# Power.net
KiCad netlist of a schematic drawn in Altium Designer
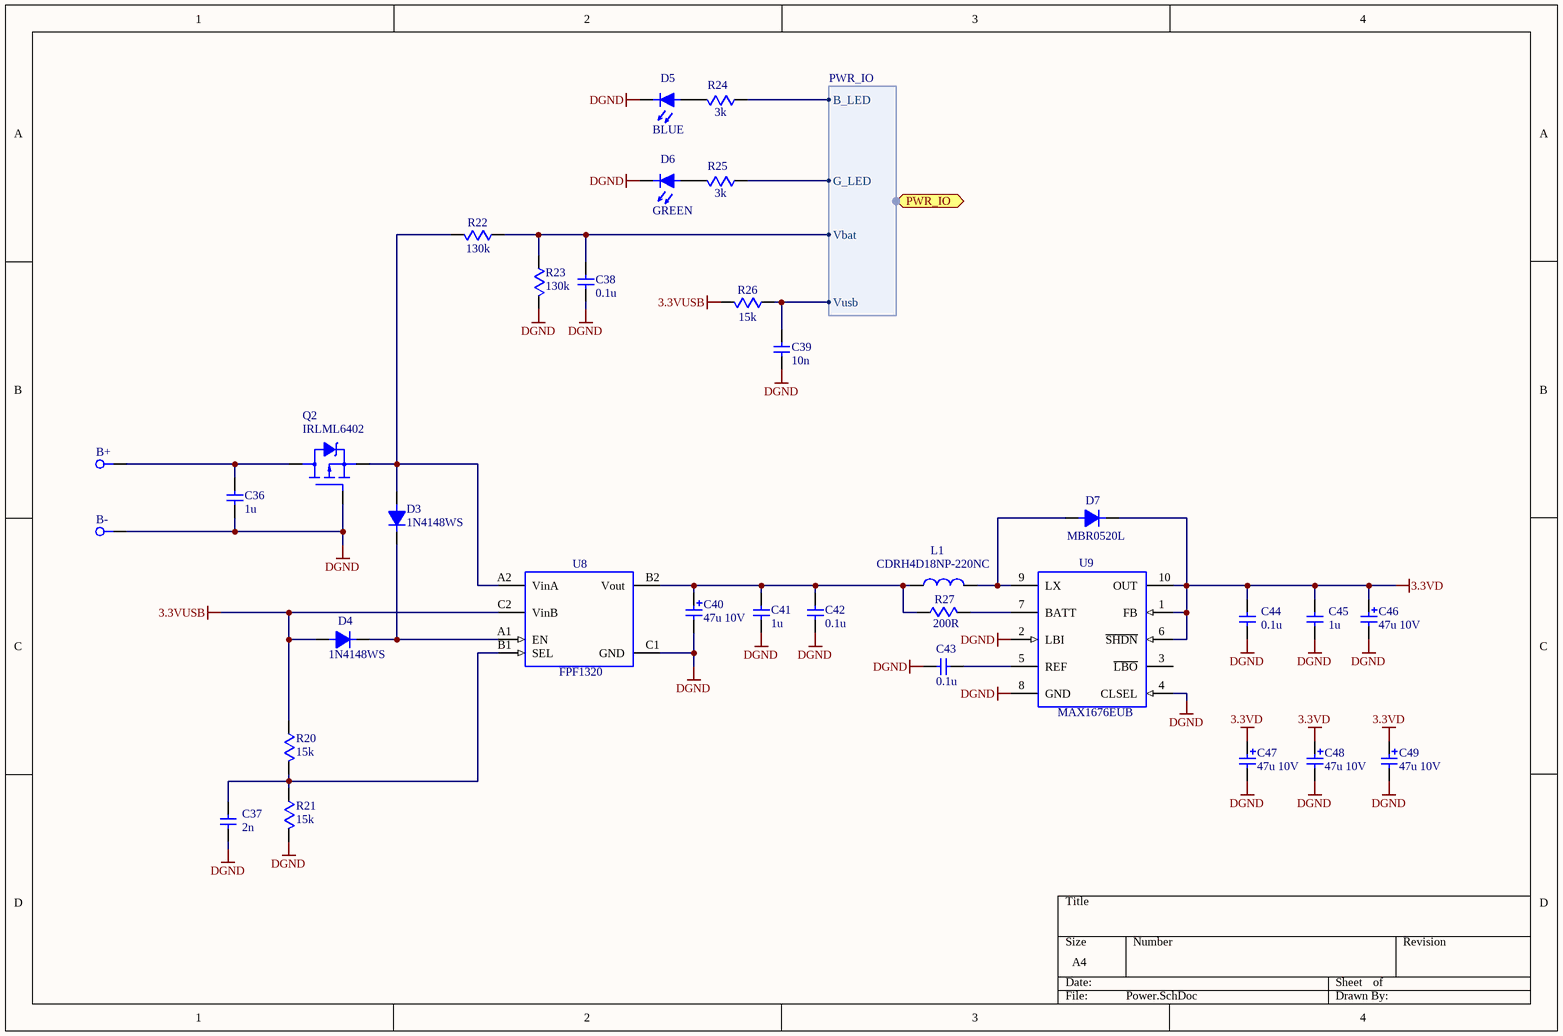
[diagram p0: Power.SchDoc]

(export (version "E")
  (design (tool "Eeschema 10.0.6"))
  (components
    (comp (ref "B+") (value "TH HOLE") (footprint "1.0MM PAD") (libsource (lib "My_lib") (part "TH HOLE")))
    (comp (ref "B-") (value "TH HOLE") (footprint "1.0MM PAD") (libsource (lib "My_lib") (part "TH HOLE")))
    (comp (ref "C36") (value "1u") (footprint "SMD/C/0603") (libsource (lib "My_lib") (part "Capacitor")))
    (comp (ref "C37") (value "2n") (footprint "SMD/C/0603") (libsource (lib "") (part "Capacitor_1")))
    (comp (ref "C38") (value "0.1u") (footprint "SMD/C/0603") (libsource (lib "My_lib") (part "Capacitor")))
    (comp (ref "C39") (value "10n") (footprint "SMD/C/0603") (libsource (lib "My_lib") (part "Capacitor")))
    (comp (ref "C40")
      (value "47u 10V")
      (footprint "SMD/C/TAJ-B")
      (libsource (lib "My_lib") (part "Capacitor Pol"))
    )
    (comp (ref "C41") (value "1u") (footprint "SMD/C/0603") (libsource (lib "My_lib") (part "Capacitor")))
    (comp (ref "C42") (value "0.1u") (footprint "SMD/C/0603") (libsource (lib "My_lib") (part "Capacitor")))
    (comp (ref "C43") (value "0.1u") (footprint "SMD/C/0603") (libsource (lib "") (part "Capacitor_1")))
    (comp (ref "C44") (value "0.1u") (footprint "SMD/C/0603") (libsource (lib "") (part "Capacitor_1")))
    (comp (ref "C45") (value "1u") (footprint "SMD/C/0603") (libsource (lib "") (part "Capacitor_1")))
    (comp (ref "C46")
      (value "47u 10V")
      (footprint "SMD/C/TAJ-B")
      (libsource (lib "My_lib") (part "Capacitor Pol"))
    )
    (comp (ref "C47")
      (value "47u 10V")
      (footprint "SMD/C/TAJ-B")
      (libsource (lib "My_lib") (part "Capacitor Pol"))
    )
    (comp (ref "C48")
      (value "47u 10V")
      (footprint "SMD/C/TAJ-B")
      (libsource (lib "My_lib") (part "Capacitor Pol"))
    )
    (comp (ref "C49")
      (value "47u 10V")
      (footprint "SMD/C/TAJ-B")
      (libsource (lib "My_lib") (part "Capacitor Pol"))
    )
    (comp (ref "D3") (value "1N4148WS") (footprint "SMD/SOD-323") (libsource (lib "My_lib") (part "Diode")))
    (comp (ref "D4") (value "1N4148WS") (footprint "SMD/SOD-323") (libsource (lib "My_lib") (part "Diode")))
    (comp (ref "D5")
      (value "BLUE")
      (footprint "SMD/LED/0603")
      (description "d3mm Ultra Brightness Blue LED")
      (libsource (lib "My_lib") (part "LED"))
    )
    (comp (ref "D6")
      (value "GREEN")
      (footprint "SMD/LED/0603")
      (description "d3mm Ultra Brightness Blue LED")
      (libsource (lib "My_lib") (part "LED"))
    )
    (comp (ref "D7") (value "MBR0520L") (footprint "SMD/SOD-123") (libsource (lib "My_lib") (part "Diode")))
    (comp (ref "L1")
      (value "CDRH4D18NP-220NC")
      (footprint "SMD\\L\\SUMIDA\\CDRH4D18")
      (libsource (lib "My_lib") (part "CDRH4D"))
    )
    (comp (ref "Q2")
      (value "IRLML6402")
      (footprint "SMD/SOT23")
      (description "P-channel HEXFET Power MOSFET")
      (libsource (lib "My_lib") (part "IRLML6402"))
    )
    (comp (ref "R20") (value "15k") (footprint "SMD/R/0603") (libsource (lib "My_lib") (part "Resistor")))
    (comp (ref "R21") (value "15k") (footprint "SMD/R/0603") (libsource (lib "My_lib") (part "Resistor")))
    (comp (ref "R22") (value "130k") (footprint "SMD/R/0603") (libsource (lib "My_lib") (part "Resistor")))
    (comp (ref "R23") (value "130k") (footprint "SMD/R/0603") (libsource (lib "My_lib") (part "Resistor")))
    (comp (ref "R24") (value "3k") (footprint "SMD/R/0603") (libsource (lib "My_lib") (part "Resistor")))
    (comp (ref "R25") (value "3k") (footprint "SMD/R/0603") (libsource (lib "My_lib") (part "Resistor")))
    (comp (ref "R26") (value "15k") (footprint "SMD/R/0603") (libsource (lib "My_lib") (part "Resistor")))
    (comp (ref "R27") (value "200R") (footprint "SMD/R/0603") (libsource (lib "My_lib") (part "Resistor")))
    (comp (ref "U8")
      (value "FPF1320")
      (footprint "SMD/BGA6/1.46x0.96MM/0.5MMP/0.25MMBALL/0.625MMH")
      (description "Power Switch")
      (libsource (lib "My_lib") (part "FPF1320"))
    )
    (comp (ref "U9")
      (value "MAX1676EUB")
      (footprint "SMD/SOP10/0.5MMP/3x3MM/4.9MMWP")
      (description "High-Efficiency, Low-Supply-Current, Compact, Step-Up DC-DC Converters")
      (libsource (lib "My_lib") (part "MAX1676EUB"))
    )
  )
  (nets
    (net (code "2") (name "/B_LED") (class "Default")
      (node (ref "R24") (pin "1") (pinfunction "1_1") (pintype "passive"))
    )
    (net (code "3") (name "/G_LED") (class "Default")
      (node (ref "R25") (pin "1") (pinfunction "1_1") (pintype "passive"))
    )
    (net (code "4") (name "/Vbat") (class "Default")
      (node (ref "C38") (pin "2") (pinfunction "2_2") (pintype "passive"))
      (node (ref "R22") (pin "1") (pinfunction "1_1") (pintype "passive"))
      (node (ref "R23") (pin "1") (pinfunction "1_1") (pintype "passive"))
    )
    (net (code "5") (name "/Vusb") (class "Default")
      (node (ref "C39") (pin "2") (pinfunction "2_2") (pintype "passive"))
      (node (ref "R26") (pin "1") (pinfunction "1_1") (pintype "passive"))
    )
    (net (code "7") (name "3.3VD") (class "Default")
      (node (ref "C44") (pin "2") (pinfunction "2_2") (pintype "passive"))
      (node (ref "C45") (pin "2") (pinfunction "2_2") (pintype "passive"))
      (node (ref "C46") (pin "P") (pinfunction "P_P") (pintype "passive"))
      (node (ref "C47") (pin "P") (pinfunction "P_P") (pintype "passive"))
      (node (ref "C48") (pin "P") (pinfunction "P_P") (pintype "passive"))
      (node (ref "C49") (pin "P") (pinfunction "P_P") (pintype "passive"))
      (node (ref "D7") (pin "C") (pinfunction "C_C") (pintype "passive"))
      (node (ref "U9") (pin "1") (pinfunction "FB_1") (pintype "input"))
      (node (ref "U9") (pin "10") (pinfunction "OUT_10") (pintype "power_in"))
      (node (ref "U9") (pin "6") (pinfunction "~{SHDN}_6") (pintype "input"))
    )
    (net (code "8") (name "3.3VUSB") (class "Default")
      (node (ref "D4") (pin "A") (pinfunction "A_A") (pintype "passive"))
      (node (ref "R20") (pin "1") (pinfunction "1_1") (pintype "passive"))
      (node (ref "R26") (pin "2") (pinfunction "2_2") (pintype "passive"))
      (node (ref "U8") (pin "C2") (pinfunction "VinB_C2") (pintype "power_in"))
    )
    (net (code "9") (name "DGND") (class "Default")
      (node (ref "B-") (pin "1") (pinfunction "1_1") (pintype "passive"))
      (node (ref "C36") (pin "1") (pinfunction "1_1") (pintype "passive"))
      (node (ref "C37") (pin "1") (pinfunction "1_1") (pintype "passive"))
      (node (ref "C38") (pin "1") (pinfunction "1_1") (pintype "passive"))
      (node (ref "C39") (pin "1") (pinfunction "1_1") (pintype "passive"))
      (node (ref "C40") (pin "M") (pinfunction "M_M") (pintype "passive"))
      (node (ref "C41") (pin "1") (pinfunction "1_1") (pintype "passive"))
      (node (ref "C42") (pin "1") (pinfunction "1_1") (pintype "passive"))
      (node (ref "C43") (pin "2") (pinfunction "2_2") (pintype "passive"))
      (node (ref "C44") (pin "1") (pinfunction "1_1") (pintype "passive"))
      (node (ref "C45") (pin "1") (pinfunction "1_1") (pintype "passive"))
      (node (ref "C46") (pin "M") (pinfunction "M_M") (pintype "passive"))
      (node (ref "C47") (pin "M") (pinfunction "M_M") (pintype "passive"))
      (node (ref "C48") (pin "M") (pinfunction "M_M") (pintype "passive"))
      (node (ref "C49") (pin "M") (pinfunction "M_M") (pintype "passive"))
      (node (ref "D5") (pin "C") (pinfunction "C_C") (pintype "passive"))
      (node (ref "D6") (pin "C") (pinfunction "C_C") (pintype "passive"))
      (node (ref "Q2") (pin "1") (pinfunction "G_1") (pintype "passive"))
      (node (ref "R21") (pin "2") (pinfunction "2_2") (pintype "passive"))
      (node (ref "R23") (pin "2") (pinfunction "2_2") (pintype "passive"))
      (node (ref "U8") (pin "C1") (pinfunction "GND_C1") (pintype "power_in"))
      (node (ref "U9") (pin "2") (pinfunction "LBI_2") (pintype "input"))
      (node (ref "U9") (pin "4") (pinfunction "CLSEL_4") (pintype "input"))
      (node (ref "U9") (pin "8") (pinfunction "GND_8") (pintype "power_in"))
    )
    (net (code "10") (name "Net-(D5-PadA)") (class "Default")
      (node (ref "D5") (pin "A") (pinfunction "A_A") (pintype "passive"))
      (node (ref "R24") (pin "2") (pinfunction "2_2") (pintype "passive"))
    )
    (net (code "11") (name "Net-(D6-PadA)") (class "Default")
      (node (ref "D6") (pin "A") (pinfunction "A_A") (pintype "passive"))
      (node (ref "R25") (pin "2") (pinfunction "2_2") (pintype "passive"))
    )
    (net (code "12") (name "Net-(Q2-D)") (class "Default")
      (node (ref "B+") (pin "1") (pinfunction "1_1") (pintype "passive"))
      (node (ref "C36") (pin "2") (pinfunction "2_2") (pintype "passive"))
      (node (ref "Q2") (pin "3") (pinfunction "D_3") (pintype "passive"))
    )
    (net (code "13") (name "Net-(Q2-S)") (class "Default")
      (node (ref "D3") (pin "A") (pinfunction "A_A") (pintype "passive"))
      (node (ref "Q2") (pin "2") (pinfunction "S_2") (pintype "passive"))
      (node (ref "R22") (pin "2") (pinfunction "2_2") (pintype "passive"))
      (node (ref "U8") (pin "A2") (pinfunction "VinA_A2") (pintype "power_in"))
    )
    (net (code "14") (name "Net-(U8-EN)") (class "Default")
      (node (ref "D3") (pin "C") (pinfunction "C_C") (pintype "passive"))
      (node (ref "D4") (pin "C") (pinfunction "C_C") (pintype "passive"))
      (node (ref "U8") (pin "A1") (pinfunction "EN_A1") (pintype "input"))
    )
    (net (code "15") (name "Net-(U8-SEL)") (class "Default")
      (node (ref "C37") (pin "2") (pinfunction "2_2") (pintype "passive"))
      (node (ref "R20") (pin "2") (pinfunction "2_2") (pintype "passive"))
      (node (ref "R21") (pin "1") (pinfunction "1_1") (pintype "passive"))
      (node (ref "U8") (pin "B1") (pinfunction "SEL_B1") (pintype "input"))
    )
    (net (code "16") (name "Net-(U8-Vout)") (class "Default")
      (node (ref "C40") (pin "P") (pinfunction "P_P") (pintype "passive"))
      (node (ref "C41") (pin "2") (pinfunction "2_2") (pintype "passive"))
      (node (ref "C42") (pin "2") (pinfunction "2_2") (pintype "passive"))
      (node (ref "L1") (pin "1") (pinfunction "1_1") (pintype "passive"))
      (node (ref "R27") (pin "1") (pinfunction "1_1") (pintype "passive"))
      (node (ref "U8") (pin "B2") (pinfunction "Vout_B2") (pintype "power_in"))
    )
    (net (code "17") (name "Net-(U9-BATT)") (class "Default")
      (node (ref "R27") (pin "2") (pinfunction "2_2") (pintype "passive"))
      (node (ref "U9") (pin "7") (pinfunction "BATT_7") (pintype "power_in"))
    )
    (net (code "18") (name "Net-(U9-LX)") (class "Default")
      (node (ref "D7") (pin "A") (pinfunction "A_A") (pintype "passive"))
      (node (ref "L1") (pin "2") (pinfunction "2_2") (pintype "passive"))
      (node (ref "U9") (pin "9") (pinfunction "LX_9") (pintype "power_in"))
    )
    (net (code "19") (name "Net-(U9-REF)") (class "Default")
      (node (ref "C43") (pin "1") (pinfunction "1_1") (pintype "passive"))
      (node (ref "U9") (pin "5") (pinfunction "REF_5") (pintype "power_in"))
    )
    (net (code "20") (name "unconnected-(U9-~{LBO}-Pad3)") (class "Default")
      (node (ref "U9") (pin "3") (pinfunction "~{LBO}_3") (pintype "open_collector"))
    )
  )
)
